# uc2B.net
KiCad netlist of a schematic drawn in Altium Designer
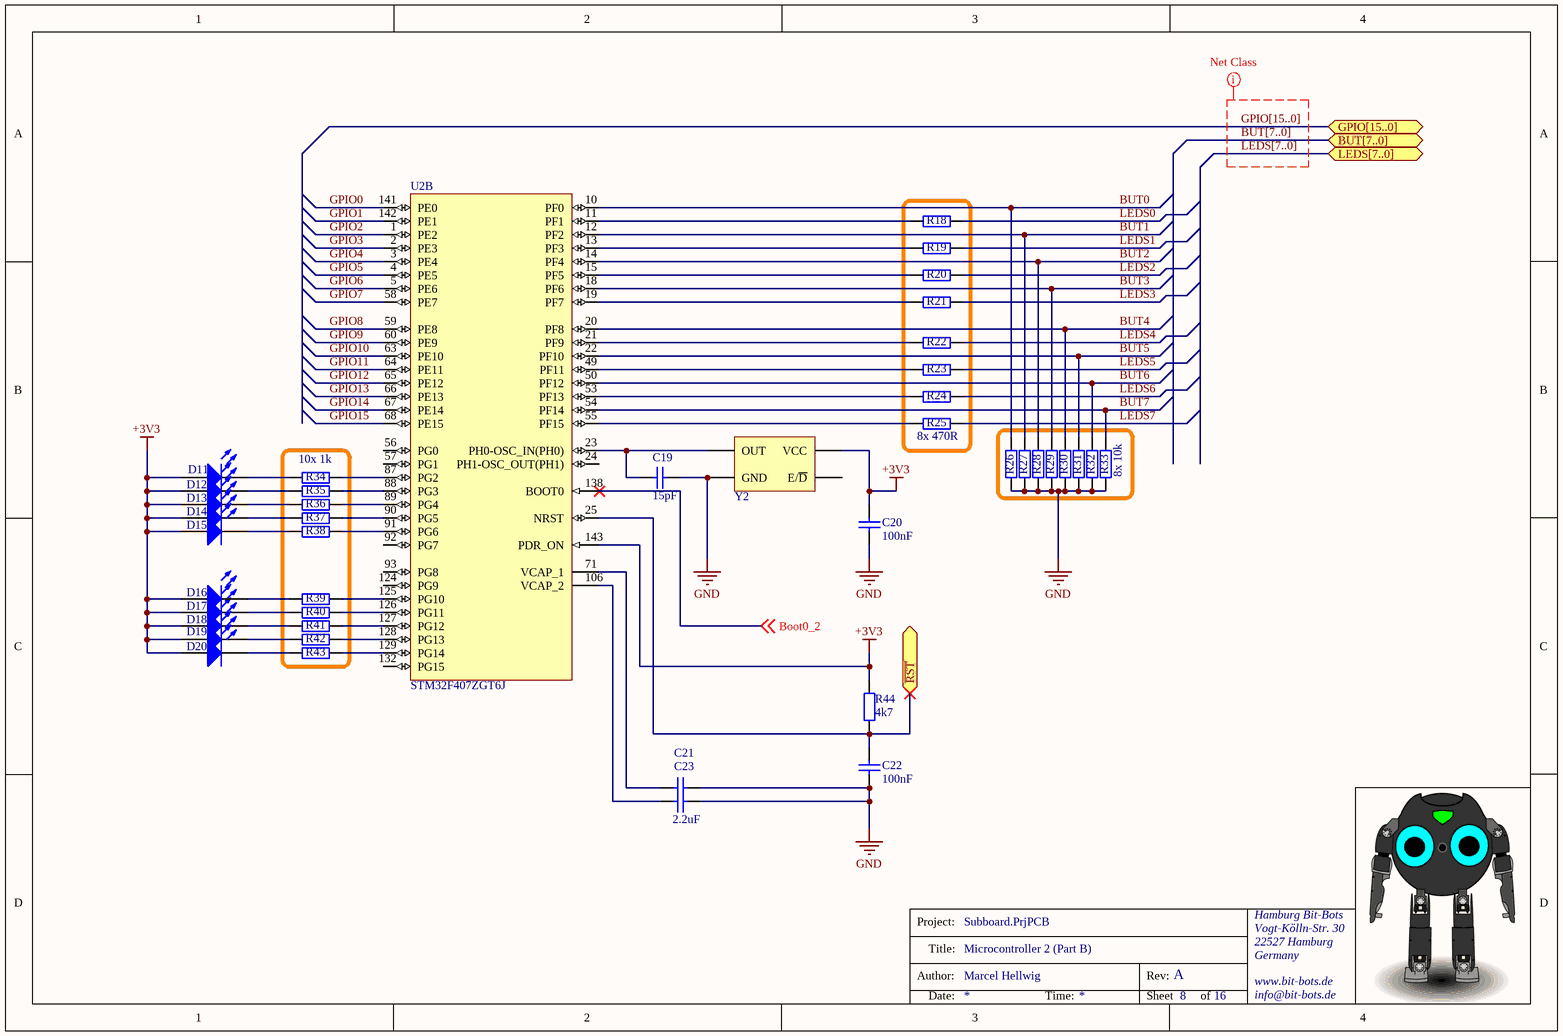
[diagram p0: uc2B.SchDoc]

(export (version "E")
  (design (tool "Eeschema 10.0.6"))
  (components
    (comp (ref "C19")
      (value "15pF")
      (footprint "C2012")
      (description "Capacitor")
      (fields
        (field (name "MANUFACTURER") "MULTICOMP")
        (field (name "MANUFACTURER PART NUMBER") "MC0805N150J500CT")
        (field (name "PUBLISHER") "Altium Limited")
      )
      (libsource (lib "Miscellaneous Devices") (part "Cap"))
    )
    (comp (ref "C20")
      (value "100nF")
      (footprint "C2012")
      (description "Capacitor")
      (fields (field (name "PUBLISHER") "Altium Limited"))
      (libsource (lib "Miscellaneous Devices") (part "Cap"))
    )
    (comp (ref "C21")
      (value "2.2uF")
      (footprint "C2012")
      (description "Capacitor")
      (fields
        (field (name "MANUFACTURER") "MULTICOMP")
        (field (name "MANUFACTURER PART NUMBER") "MC0805B225K250CT")
        (field (name "PUBLISHER") "Altium Limited")
      )
      (libsource (lib "Miscellaneous Devices") (part "Cap"))
    )
    (comp (ref "C22")
      (value "100nF")
      (footprint "C2012")
      (description "Capacitor")
      (fields
        (field (name "MANUFACTURER") "MULTICOMP")
        (field (name "MANUFACTURER PART NUMBER") "MC0805B104K500CT")
        (field (name "PUBLISHER") "Altium Limited")
      )
      (libsource (lib "Miscellaneous Devices") (part "Cap"))
    )
    (comp (ref "C23")
      (value "2.2uF")
      (footprint "C2012")
      (description "Capacitor")
      (fields
        (field (name "MANUFACTURER") "MULTICOMP")
        (field (name "MANUFACTURER PART NUMBER") "MC0805B225K250CT")
        (field (name "PUBLISHER") "Altium Limited")
      )
      (libsource (lib "Miscellaneous Devices") (part "Cap"))
    )
    (comp (ref "D11")
      (value "Green")
      (footprint "MLCC2")
      (description "Typical INFRARED GaAs LED")
      (fields
        (field (name "MANUFACTURER") "VISHAY")
        (field (name "MANUFACTURER PART NUMBER") "VLMC3100-GS08")
        (field (name "PUBLISHER") "Altium Limited")
      )
      (libsource (lib "Miscellaneous Devices") (part "LED0"))
    )
    (comp (ref "D12")
      (value "Green")
      (footprint "MLCC2")
      (description "Typical INFRARED GaAs LED")
      (fields
        (field (name "MANUFACTURER") "VISHAY")
        (field (name "MANUFACTURER PART NUMBER") "VLMC3100-GS08")
        (field (name "PUBLISHER") "Altium Limited")
      )
      (libsource (lib "Miscellaneous Devices") (part "LED0"))
    )
    (comp (ref "D13")
      (value "Green")
      (footprint "MLCC2")
      (description "Typical INFRARED GaAs LED")
      (fields
        (field (name "MANUFACTURER") "VISHAY")
        (field (name "MANUFACTURER PART NUMBER") "VLMC3100-GS08")
        (field (name "PUBLISHER") "Altium Limited")
      )
      (libsource (lib "Miscellaneous Devices") (part "LED0"))
    )
    (comp (ref "D14")
      (value "Green")
      (footprint "MLCC2")
      (description "Typical INFRARED GaAs LED")
      (fields
        (field (name "MANUFACTURER") "VISHAY")
        (field (name "MANUFACTURER PART NUMBER") "VLMC3100-GS08")
        (field (name "PUBLISHER") "Altium Limited")
      )
      (libsource (lib "Miscellaneous Devices") (part "LED0"))
    )
    (comp (ref "D15")
      (value "Green")
      (footprint "MLCC2")
      (description "Typical INFRARED GaAs LED")
      (fields
        (field (name "MANUFACTURER") "VISHAY")
        (field (name "MANUFACTURER PART NUMBER") "VLMC3100-GS08")
        (field (name "PUBLISHER") "Altium Limited")
      )
      (libsource (lib "Miscellaneous Devices") (part "LED0"))
    )
    (comp (ref "D16")
      (value "Green")
      (footprint "MLCC2")
      (description "Typical INFRARED GaAs LED")
      (fields
        (field (name "MANUFACTURER") "VISHAY")
        (field (name "MANUFACTURER PART NUMBER") "VLMC3100-GS08")
        (field (name "PUBLISHER") "Altium Limited")
      )
      (libsource (lib "Miscellaneous Devices") (part "LED0"))
    )
    (comp (ref "D17")
      (value "Green")
      (footprint "MLCC2")
      (description "Typical INFRARED GaAs LED")
      (fields
        (field (name "MANUFACTURER") "VISHAY")
        (field (name "MANUFACTURER PART NUMBER") "VLMC3100-GS08")
        (field (name "PUBLISHER") "Altium Limited")
      )
      (libsource (lib "Miscellaneous Devices") (part "LED0"))
    )
    (comp (ref "D18")
      (value "Green")
      (footprint "MLCC2")
      (description "Typical INFRARED GaAs LED")
      (fields
        (field (name "MANUFACTURER") "VISHAY")
        (field (name "MANUFACTURER PART NUMBER") "VLMC3100-GS08")
        (field (name "PUBLISHER") "Altium Limited")
      )
      (libsource (lib "Miscellaneous Devices") (part "LED0"))
    )
    (comp (ref "D19")
      (value "Green")
      (footprint "MLCC2")
      (description "Typical INFRARED GaAs LED")
      (fields
        (field (name "MANUFACTURER") "VISHAY")
        (field (name "MANUFACTURER PART NUMBER") "VLMC3100-GS08")
        (field (name "PUBLISHER") "Altium Limited")
      )
      (libsource (lib "Miscellaneous Devices") (part "LED0"))
    )
    (comp (ref "D20")
      (value "Green")
      (footprint "MLCC2")
      (description "Typical INFRARED GaAs LED")
      (fields
        (field (name "MANUFACTURER") "VISHAY")
        (field (name "MANUFACTURER PART NUMBER") "VLMC3100-GS08")
        (field (name "PUBLISHER") "Altium Limited")
      )
      (libsource (lib "Miscellaneous Devices") (part "LED0"))
    )
    (comp (ref "R18")
      (value "470R")
      (footprint "R2012")
      (description "Resistor")
      (fields
        (field (name "MANUFACTURER") "MULTICOMP")
        (field (name "MANUFACTURER PART NUMBER") "MCSR08X4700FTL")
        (field (name "PUBLISHER") "Altium Limited")
      )
      (libsource (lib "") (part "Res2_2"))
    )
    (comp (ref "R19")
      (value "470R")
      (footprint "R2012")
      (description "Resistor")
      (fields
        (field (name "MANUFACTURER") "MULTICOMP")
        (field (name "MANUFACTURER PART NUMBER") "MCSR08X4700FTL")
        (field (name "PUBLISHER") "Altium Limited")
      )
      (libsource (lib "") (part "Res2_2"))
    )
    (comp (ref "R20")
      (value "470R")
      (footprint "R2012")
      (description "Resistor")
      (fields
        (field (name "MANUFACTURER") "MULTICOMP")
        (field (name "MANUFACTURER PART NUMBER") "MCSR08X4700FTL")
        (field (name "PUBLISHER") "Altium Limited")
      )
      (libsource (lib "") (part "Res2_2"))
    )
    (comp (ref "R21")
      (value "470R")
      (footprint "R2012")
      (description "Resistor")
      (fields
        (field (name "MANUFACTURER") "MULTICOMP")
        (field (name "MANUFACTURER PART NUMBER") "MCSR08X4700FTL")
        (field (name "PUBLISHER") "Altium Limited")
      )
      (libsource (lib "") (part "Res2_2"))
    )
    (comp (ref "R22")
      (value "470R")
      (footprint "R2012")
      (description "Resistor")
      (fields
        (field (name "MANUFACTURER") "MULTICOMP")
        (field (name "MANUFACTURER PART NUMBER") "MCSR08X4700FTL")
        (field (name "PUBLISHER") "Altium Limited")
      )
      (libsource (lib "") (part "Res2_2"))
    )
    (comp (ref "R23")
      (value "470R")
      (footprint "R2012")
      (description "Resistor")
      (fields
        (field (name "MANUFACTURER") "MULTICOMP")
        (field (name "MANUFACTURER PART NUMBER") "MCSR08X4700FTL")
        (field (name "PUBLISHER") "Altium Limited")
      )
      (libsource (lib "") (part "Res2_2"))
    )
    (comp (ref "R24")
      (value "470R")
      (footprint "R2012")
      (description "Resistor")
      (fields
        (field (name "MANUFACTURER") "MULTICOMP")
        (field (name "MANUFACTURER PART NUMBER") "MCSR08X4700FTL")
        (field (name "PUBLISHER") "Altium Limited")
      )
      (libsource (lib "") (part "Res2_2"))
    )
    (comp (ref "R25")
      (value "470R")
      (footprint "R2012")
      (description "Resistor")
      (fields
        (field (name "MANUFACTURER") "MULTICOMP")
        (field (name "MANUFACTURER PART NUMBER") "MCSR08X4700FTL")
        (field (name "PUBLISHER") "Altium Limited")
      )
      (libsource (lib "") (part "Res2_2"))
    )
    (comp (ref "R26")
      (value "10k")
      (footprint "R2012")
      (description "Resistor")
      (fields
        (field (name "MANUFACTURER") "MULTICOMP")
        (field (name "MANUFACTURER PART NUMBER") "MC01W0805110K")
        (field (name "PUBLISHER") "Altium Limited")
      )
      (libsource (lib "Miscellaneous Devices") (part "Res2"))
    )
    (comp (ref "R27")
      (value "10k")
      (footprint "R2012")
      (description "Resistor")
      (fields
        (field (name "MANUFACTURER") "MULTICOMP")
        (field (name "MANUFACTURER PART NUMBER") "MC01W0805110K")
        (field (name "PUBLISHER") "Altium Limited")
      )
      (libsource (lib "Miscellaneous Devices") (part "Res2"))
    )
    (comp (ref "R28")
      (value "10k")
      (footprint "R2012")
      (description "Resistor")
      (fields
        (field (name "MANUFACTURER") "MULTICOMP")
        (field (name "MANUFACTURER PART NUMBER") "MC01W0805110K")
        (field (name "PUBLISHER") "Altium Limited")
      )
      (libsource (lib "Miscellaneous Devices") (part "Res2"))
    )
    (comp (ref "R29")
      (value "10k")
      (footprint "R2012")
      (description "Resistor")
      (fields
        (field (name "MANUFACTURER") "MULTICOMP")
        (field (name "MANUFACTURER PART NUMBER") "MC01W0805110K")
        (field (name "PUBLISHER") "Altium Limited")
      )
      (libsource (lib "Miscellaneous Devices") (part "Res2"))
    )
    (comp (ref "R30")
      (value "10k")
      (footprint "R2012")
      (description "Resistor")
      (fields
        (field (name "MANUFACTURER") "MULTICOMP")
        (field (name "MANUFACTURER PART NUMBER") "MC01W0805110K")
        (field (name "PUBLISHER") "Altium Limited")
      )
      (libsource (lib "Miscellaneous Devices") (part "Res2"))
    )
    (comp (ref "R31")
      (value "10k")
      (footprint "R2012")
      (description "Resistor")
      (fields
        (field (name "MANUFACTURER") "MULTICOMP")
        (field (name "MANUFACTURER PART NUMBER") "MC01W0805110K")
        (field (name "PUBLISHER") "Altium Limited")
      )
      (libsource (lib "Miscellaneous Devices") (part "Res2"))
    )
    (comp (ref "R32")
      (value "10k")
      (footprint "R2012")
      (description "Resistor")
      (fields
        (field (name "MANUFACTURER") "MULTICOMP")
        (field (name "MANUFACTURER PART NUMBER") "MC01W0805110K")
        (field (name "PUBLISHER") "Altium Limited")
      )
      (libsource (lib "Miscellaneous Devices") (part "Res2"))
    )
    (comp (ref "R33")
      (value "10k")
      (footprint "R2012")
      (description "Resistor")
      (fields
        (field (name "MANUFACTURER") "MULTICOMP")
        (field (name "MANUFACTURER PART NUMBER") "MC01W0805110K")
        (field (name "PUBLISHER") "Altium Limited")
      )
      (libsource (lib "Miscellaneous Devices") (part "Res2"))
    )
    (comp (ref "R34")
      (value "1k")
      (footprint "R2012")
      (description "Resistor")
      (fields
        (field (name "MANUFACTURER") "MULTICOMP")
        (field (name "MANUFACTURER PART NUMBER") "MC01W0805110K")
        (field (name "PUBLISHER") "Altium Limited")
      )
      (libsource (lib "") (part "Res2_1"))
    )
    (comp (ref "R35")
      (value "1k")
      (footprint "R2012")
      (description "Resistor")
      (fields
        (field (name "MANUFACTURER") "MULTICOMP")
        (field (name "MANUFACTURER PART NUMBER") "MC01W0805110K")
        (field (name "PUBLISHER") "Altium Limited")
      )
      (libsource (lib "") (part "Res2_1"))
    )
    (comp (ref "R36")
      (value "1k")
      (footprint "R2012")
      (description "Resistor")
      (fields
        (field (name "MANUFACTURER") "MULTICOMP")
        (field (name "MANUFACTURER PART NUMBER") "MC01W0805110K")
        (field (name "PUBLISHER") "Altium Limited")
      )
      (libsource (lib "") (part "Res2_1"))
    )
    (comp (ref "R37")
      (value "1k")
      (footprint "R2012")
      (description "Resistor")
      (fields
        (field (name "MANUFACTURER") "MULTICOMP")
        (field (name "MANUFACTURER PART NUMBER") "MC01W0805110K")
        (field (name "PUBLISHER") "Altium Limited")
      )
      (libsource (lib "") (part "Res2_1"))
    )
    (comp (ref "R38")
      (value "1k")
      (footprint "R2012")
      (description "Resistor")
      (fields
        (field (name "MANUFACTURER") "MULTICOMP")
        (field (name "MANUFACTURER PART NUMBER") "MC01W0805110K")
        (field (name "PUBLISHER") "Altium Limited")
      )
      (libsource (lib "") (part "Res2_1"))
    )
    (comp (ref "R39")
      (value "1k")
      (footprint "R2012")
      (description "Resistor")
      (fields
        (field (name "MANUFACTURER") "MULTICOMP")
        (field (name "MANUFACTURER PART NUMBER") "MC01W0805110K")
        (field (name "PUBLISHER") "Altium Limited")
      )
      (libsource (lib "") (part "Res2_1"))
    )
    (comp (ref "R40")
      (value "1k")
      (footprint "R2012")
      (description "Resistor")
      (fields
        (field (name "MANUFACTURER") "MULTICOMP")
        (field (name "MANUFACTURER PART NUMBER") "MC01W0805110K")
        (field (name "PUBLISHER") "Altium Limited")
      )
      (libsource (lib "") (part "Res2_1"))
    )
    (comp (ref "R41")
      (value "1k")
      (footprint "R2012")
      (description "Resistor")
      (fields
        (field (name "MANUFACTURER") "MULTICOMP")
        (field (name "MANUFACTURER PART NUMBER") "MC01W0805110K")
        (field (name "PUBLISHER") "Altium Limited")
      )
      (libsource (lib "") (part "Res2_1"))
    )
    (comp (ref "R42")
      (value "1k")
      (footprint "R2012")
      (description "Resistor")
      (fields
        (field (name "MANUFACTURER") "MULTICOMP")
        (field (name "MANUFACTURER PART NUMBER") "MC01W0805110K")
        (field (name "PUBLISHER") "Altium Limited")
      )
      (libsource (lib "") (part "Res2_1"))
    )
    (comp (ref "R43")
      (value "1k")
      (footprint "R2012")
      (description "Resistor")
      (fields
        (field (name "MANUFACTURER") "MULTICOMP")
        (field (name "MANUFACTURER PART NUMBER") "MC01W0805110K")
        (field (name "PUBLISHER") "Altium Limited")
      )
      (libsource (lib "") (part "Res2_1"))
    )
    (comp (ref "R44")
      (value "4k7")
      (footprint "R2012")
      (description "Resistor")
      (fields
        (field (name "MANUFACTURER") "MULTICOMP")
        (field (name "MANUFACTURER PART NUMBER") "MC01W080514K7")
        (field (name "PUBLISHER") "Altium Limited")
      )
      (libsource (lib "Miscellaneous Devices") (part "Res2"))
    )
    (comp (ref "U2")
      (value "STM32F407ZGT6J")
      (footprint "STM-LQFP144_M")
      (fields (field (name "MANUFACTURER") "STMicroelectronics"))
      (libsource (lib "Altium Content Vault") (part "CMP-0243-00063-2"))
    )
    (comp (ref "Y2")
      (value "FXO-HC736R-16")
      (footprint "FXO-HC73")
      (description "Oscillator with Enable Input")
      (libsource (lib "bitbots") (part "Oszillator"))
    )
  )
  (nets
    (net (code "1") (name "+3V3") (class "Default")
      (node (ref "C20") (pin "1") (pinfunction "1_1") (pintype "passive"))
      (node (ref "D11") (pin "1") (pinfunction "A_1") (pintype "passive"))
      (node (ref "D12") (pin "1") (pinfunction "A_1") (pintype "passive"))
      (node (ref "D13") (pin "1") (pinfunction "A_1") (pintype "passive"))
      (node (ref "D14") (pin "1") (pinfunction "A_1") (pintype "passive"))
      (node (ref "D15") (pin "1") (pinfunction "A_1") (pintype "passive"))
      (node (ref "D16") (pin "1") (pinfunction "A_1") (pintype "passive"))
      (node (ref "D17") (pin "1") (pinfunction "A_1") (pintype "passive"))
      (node (ref "D18") (pin "1") (pinfunction "A_1") (pintype "passive"))
      (node (ref "D19") (pin "1") (pinfunction "A_1") (pintype "passive"))
      (node (ref "D20") (pin "1") (pinfunction "A_1") (pintype "passive"))
      (node (ref "R44") (pin "1") (pinfunction "1_1") (pintype "passive"))
      (node (ref "U2") (pin "143") (pinfunction "PDR_ON_143") (pintype "input"))
      (node (ref "Y2") (pin "4") (pinfunction "VCC_4") (pintype "passive"))
    )
    (net (code "2") (name "/BUT0") (class "Default")
      (node (ref "R26") (pin "1") (pinfunction "1_1") (pintype "passive"))
      (node (ref "U2") (pin "10") (pinfunction "PF0_10") (pintype "bidirectional"))
    )
    (net (code "3") (name "/BUT1") (class "Default")
      (node (ref "R27") (pin "1") (pinfunction "1_1") (pintype "passive"))
      (node (ref "U2") (pin "12") (pinfunction "PF2_12") (pintype "bidirectional"))
    )
    (net (code "4") (name "/BUT2") (class "Default")
      (node (ref "R28") (pin "1") (pinfunction "1_1") (pintype "passive"))
      (node (ref "U2") (pin "14") (pinfunction "PF4_14") (pintype "bidirectional"))
    )
    (net (code "5") (name "/BUT3") (class "Default")
      (node (ref "R29") (pin "1") (pinfunction "1_1") (pintype "passive"))
      (node (ref "U2") (pin "18") (pinfunction "PF6_18") (pintype "bidirectional"))
    )
    (net (code "6") (name "/BUT4") (class "Default")
      (node (ref "R30") (pin "1") (pinfunction "1_1") (pintype "passive"))
      (node (ref "U2") (pin "20") (pinfunction "PF8_20") (pintype "bidirectional"))
    )
    (net (code "7") (name "/BUT5") (class "Default")
      (node (ref "R31") (pin "1") (pinfunction "1_1") (pintype "passive"))
      (node (ref "U2") (pin "22") (pinfunction "PF10_22") (pintype "bidirectional"))
    )
    (net (code "8") (name "/BUT6") (class "Default")
      (node (ref "R32") (pin "1") (pinfunction "1_1") (pintype "passive"))
      (node (ref "U2") (pin "50") (pinfunction "PF12_50") (pintype "bidirectional"))
    )
    (net (code "9") (name "/BUT7") (class "Default")
      (node (ref "R33") (pin "1") (pinfunction "1_1") (pintype "passive"))
      (node (ref "U2") (pin "54") (pinfunction "PF14_54") (pintype "bidirectional"))
    )
    (net (code "11") (name "/GPIO0") (class "Default")
      (node (ref "U2") (pin "141") (pinfunction "PE0_141") (pintype "bidirectional"))
    )
    (net (code "12") (name "/GPIO1") (class "Default")
      (node (ref "U2") (pin "142") (pinfunction "PE1_142") (pintype "bidirectional"))
    )
    (net (code "13") (name "/GPIO2") (class "Default")
      (node (ref "U2") (pin "1") (pinfunction "PE2_1") (pintype "bidirectional"))
    )
    (net (code "14") (name "/GPIO3") (class "Default")
      (node (ref "U2") (pin "2") (pinfunction "PE3_2") (pintype "bidirectional"))
    )
    (net (code "15") (name "/GPIO4") (class "Default")
      (node (ref "U2") (pin "3") (pinfunction "PE4_3") (pintype "bidirectional"))
    )
    (net (code "16") (name "/GPIO5") (class "Default")
      (node (ref "U2") (pin "4") (pinfunction "PE5_4") (pintype "bidirectional"))
    )
    (net (code "17") (name "/GPIO6") (class "Default")
      (node (ref "U2") (pin "5") (pinfunction "PE6_5") (pintype "bidirectional"))
    )
    (net (code "18") (name "/GPIO7") (class "Default")
      (node (ref "U2") (pin "58") (pinfunction "PE7_58") (pintype "bidirectional"))
    )
    (net (code "19") (name "/GPIO8") (class "Default")
      (node (ref "U2") (pin "59") (pinfunction "PE8_59") (pintype "bidirectional"))
    )
    (net (code "20") (name "/GPIO9") (class "Default")
      (node (ref "U2") (pin "60") (pinfunction "PE9_60") (pintype "bidirectional"))
    )
    (net (code "21") (name "/GPIO10") (class "Default")
      (node (ref "U2") (pin "63") (pinfunction "PE10_63") (pintype "bidirectional"))
    )
    (net (code "22") (name "/GPIO11") (class "Default")
      (node (ref "U2") (pin "64") (pinfunction "PE11_64") (pintype "bidirectional"))
    )
    (net (code "23") (name "/GPIO12") (class "Default")
      (node (ref "U2") (pin "65") (pinfunction "PE12_65") (pintype "bidirectional"))
    )
    (net (code "24") (name "/GPIO13") (class "Default")
      (node (ref "U2") (pin "66") (pinfunction "PE13_66") (pintype "bidirectional"))
    )
    (net (code "25") (name "/GPIO14") (class "Default")
      (node (ref "U2") (pin "67") (pinfunction "PE14_67") (pintype "bidirectional"))
    )
    (net (code "26") (name "/GPIO15") (class "Default")
      (node (ref "U2") (pin "68") (pinfunction "PE15_68") (pintype "bidirectional"))
    )
    (net (code "28") (name "/LEDS0") (class "Default")
      (node (ref "R18") (pin "2") (pinfunction "2_2") (pintype "passive"))
    )
    (net (code "29") (name "/LEDS1") (class "Default")
      (node (ref "R19") (pin "2") (pinfunction "2_2") (pintype "passive"))
    )
    (net (code "30") (name "/LEDS2") (class "Default")
      (node (ref "R20") (pin "2") (pinfunction "2_2") (pintype "passive"))
    )
    (net (code "31") (name "/LEDS3") (class "Default")
      (node (ref "R21") (pin "2") (pinfunction "2_2") (pintype "passive"))
    )
    (net (code "32") (name "/LEDS4") (class "Default")
      (node (ref "R22") (pin "2") (pinfunction "2_2") (pintype "passive"))
    )
    (net (code "33") (name "/LEDS5") (class "Default")
      (node (ref "R23") (pin "2") (pinfunction "2_2") (pintype "passive"))
    )
    (net (code "34") (name "/LEDS6") (class "Default")
      (node (ref "R24") (pin "2") (pinfunction "2_2") (pintype "passive"))
    )
    (net (code "35") (name "/LEDS7") (class "Default")
      (node (ref "R25") (pin "2") (pinfunction "2_2") (pintype "passive"))
    )
    (net (code "37") (name "/RST") (class "Default")
      (node (ref "C22") (pin "2") (pinfunction "2_2") (pintype "passive"))
      (node (ref "R44") (pin "2") (pinfunction "2_2") (pintype "passive"))
      (node (ref "U2") (pin "25") (pinfunction "NRST_25") (pintype "bidirectional"))
    )
    (net (code "38") (name "Boot0_2") (class "Default")
      (node (ref "U2") (pin "138") (pinfunction "BOOT0_138") (pintype "input"))
    )
    (net (code "39") (name "GND") (class "Default")
      (node (ref "C19") (pin "1") (pinfunction "1_1") (pintype "passive"))
      (node (ref "C20") (pin "2") (pinfunction "2_2") (pintype "passive"))
      (node (ref "C21") (pin "2") (pinfunction "2_2") (pintype "passive"))
      (node (ref "C22") (pin "1") (pinfunction "1_1") (pintype "passive"))
      (node (ref "C23") (pin "2") (pinfunction "2_2") (pintype "passive"))
      (node (ref "R26") (pin "2") (pinfunction "2_2") (pintype "passive"))
      (node (ref "R27") (pin "2") (pinfunction "2_2") (pintype "passive"))
      (node (ref "R28") (pin "2") (pinfunction "2_2") (pintype "passive"))
      (node (ref "R29") (pin "2") (pinfunction "2_2") (pintype "passive"))
      (node (ref "R30") (pin "2") (pinfunction "2_2") (pintype "passive"))
      (node (ref "R31") (pin "2") (pinfunction "2_2") (pintype "passive"))
      (node (ref "R32") (pin "2") (pinfunction "2_2") (pintype "passive"))
      (node (ref "R33") (pin "2") (pinfunction "2_2") (pintype "passive"))
      (node (ref "Y2") (pin "2") (pinfunction "GND_2") (pintype "passive"))
    )
    (net (code "40") (name "Net-(D11-K)") (class "Default")
      (node (ref "D11") (pin "2") (pinfunction "K_2") (pintype "passive"))
      (node (ref "R34") (pin "2") (pinfunction "2_2") (pintype "passive"))
    )
    (net (code "41") (name "Net-(D12-K)") (class "Default")
      (node (ref "D12") (pin "2") (pinfunction "K_2") (pintype "passive"))
      (node (ref "R35") (pin "2") (pinfunction "2_2") (pintype "passive"))
    )
    (net (code "42") (name "Net-(D13-K)") (class "Default")
      (node (ref "D13") (pin "2") (pinfunction "K_2") (pintype "passive"))
      (node (ref "R36") (pin "2") (pinfunction "2_2") (pintype "passive"))
    )
    (net (code "43") (name "Net-(D14-K)") (class "Default")
      (node (ref "D14") (pin "2") (pinfunction "K_2") (pintype "passive"))
      (node (ref "R37") (pin "2") (pinfunction "2_2") (pintype "passive"))
    )
    (net (code "44") (name "Net-(D15-K)") (class "Default")
      (node (ref "D15") (pin "2") (pinfunction "K_2") (pintype "passive"))
      (node (ref "R38") (pin "2") (pinfunction "2_2") (pintype "passive"))
    )
    (net (code "45") (name "Net-(D16-K)") (class "Default")
      (node (ref "D16") (pin "2") (pinfunction "K_2") (pintype "passive"))
      (node (ref "R39") (pin "2") (pinfunction "2_2") (pintype "passive"))
    )
    (net (code "46") (name "Net-(D17-K)") (class "Default")
      (node (ref "D17") (pin "2") (pinfunction "K_2") (pintype "passive"))
      (node (ref "R40") (pin "2") (pinfunction "2_2") (pintype "passive"))
    )
    (net (code "47") (name "Net-(D18-K)") (class "Default")
      (node (ref "D18") (pin "2") (pinfunction "K_2") (pintype "passive"))
      (node (ref "R41") (pin "2") (pinfunction "2_2") (pintype "passive"))
    )
    (net (code "48") (name "Net-(D19-K)") (class "Default")
      (node (ref "D19") (pin "2") (pinfunction "K_2") (pintype "passive"))
      (node (ref "R42") (pin "2") (pinfunction "2_2") (pintype "passive"))
    )
    (net (code "49") (name "Net-(D20-K)") (class "Default")
      (node (ref "D20") (pin "2") (pinfunction "K_2") (pintype "passive"))
      (node (ref "R43") (pin "2") (pinfunction "2_2") (pintype "passive"))
    )
    (net (code "50") (name "Net-(U2B-PF1)") (class "Default")
      (node (ref "R18") (pin "1") (pinfunction "1_1") (pintype "passive"))
      (node (ref "U2") (pin "11") (pinfunction "PF1_11") (pintype "bidirectional"))
    )
    (net (code "51") (name "Net-(U2B-PF3)") (class "Default")
      (node (ref "R19") (pin "1") (pinfunction "1_1") (pintype "passive"))
      (node (ref "U2") (pin "13") (pinfunction "PF3_13") (pintype "bidirectional"))
    )
    (net (code "52") (name "Net-(U2B-PF5)") (class "Default")
      (node (ref "R20") (pin "1") (pinfunction "1_1") (pintype "passive"))
      (node (ref "U2") (pin "15") (pinfunction "PF5_15") (pintype "bidirectional"))
    )
    (net (code "53") (name "Net-(U2B-PF7)") (class "Default")
      (node (ref "R21") (pin "1") (pinfunction "1_1") (pintype "passive"))
      (node (ref "U2") (pin "19") (pinfunction "PF7_19") (pintype "bidirectional"))
    )
    (net (code "54") (name "Net-(U2B-PF9)") (class "Default")
      (node (ref "R22") (pin "1") (pinfunction "1_1") (pintype "passive"))
      (node (ref "U2") (pin "21") (pinfunction "PF9_21") (pintype "bidirectional"))
    )
    (net (code "55") (name "Net-(U2B-PF11)") (class "Default")
      (node (ref "R23") (pin "1") (pinfunction "1_1") (pintype "passive"))
      (node (ref "U2") (pin "49") (pinfunction "PF11_49") (pintype "bidirectional"))
    )
    (net (code "56") (name "Net-(U2B-PF13)") (class "Default")
      (node (ref "R24") (pin "1") (pinfunction "1_1") (pintype "passive"))
      (node (ref "U2") (pin "53") (pinfunction "PF13_53") (pintype "bidirectional"))
    )
    (net (code "57") (name "Net-(U2B-PF15)") (class "Default")
      (node (ref "R25") (pin "1") (pinfunction "1_1") (pintype "passive"))
      (node (ref "U2") (pin "55") (pinfunction "PF15_55") (pintype "bidirectional"))
    )
    (net (code "58") (name "Net-(U2B-PG2)") (class "Default")
      (node (ref "R34") (pin "1") (pinfunction "1_1") (pintype "passive"))
      (node (ref "U2") (pin "87") (pinfunction "PG2_87") (pintype "bidirectional"))
    )
    (net (code "59") (name "Net-(U2B-PG3)") (class "Default")
      (node (ref "R35") (pin "1") (pinfunction "1_1") (pintype "passive"))
      (node (ref "U2") (pin "88") (pinfunction "PG3_88") (pintype "bidirectional"))
    )
    (net (code "60") (name "Net-(U2B-PG4)") (class "Default")
      (node (ref "R36") (pin "1") (pinfunction "1_1") (pintype "passive"))
      (node (ref "U2") (pin "89") (pinfunction "PG4_89") (pintype "bidirectional"))
    )
    (net (code "61") (name "Net-(U2B-PG5)") (class "Default")
      (node (ref "R37") (pin "1") (pinfunction "1_1") (pintype "passive"))
      (node (ref "U2") (pin "90") (pinfunction "PG5_90") (pintype "bidirectional"))
    )
    (net (code "62") (name "Net-(U2B-PG6)") (class "Default")
      (node (ref "R38") (pin "1") (pinfunction "1_1") (pintype "passive"))
      (node (ref "U2") (pin "91") (pinfunction "PG6_91") (pintype "bidirectional"))
    )
    (net (code "63") (name "Net-(U2B-PG10)") (class "Default")
      (node (ref "R39") (pin "1") (pinfunction "1_1") (pintype "passive"))
      (node (ref "U2") (pin "125") (pinfunction "PG10_125") (pintype "bidirectional"))
    )
    (net (code "64") (name "Net-(U2B-PG11)") (class "Default")
      (node (ref "R40") (pin "1") (pinfunction "1_1") (pintype "passive"))
      (node (ref "U2") (pin "126") (pinfunction "PG11_126") (pintype "bidirectional"))
    )
    (net (code "65") (name "Net-(U2B-PG12)") (class "Default")
      (node (ref "R41") (pin "1") (pinfunction "1_1") (pintype "passive"))
      (node (ref "U2") (pin "127") (pinfunction "PG12_127") (pintype "bidirectional"))
    )
    (net (code "66") (name "Net-(U2B-PG13)") (class "Default")
      (node (ref "R42") (pin "1") (pinfunction "1_1") (pintype "passive"))
      (node (ref "U2") (pin "128") (pinfunction "PG13_128") (pintype "bidirectional"))
    )
    (net (code "67") (name "Net-(U2B-PG14)") (class "Default")
      (node (ref "R43") (pin "1") (pinfunction "1_1") (pintype "passive"))
      (node (ref "U2") (pin "129") (pinfunction "PG14_129") (pintype "bidirectional"))
    )
    (net (code "68") (name "Net-(U2B-PH0-OSC_IN(PH0))") (class "Default")
      (node (ref "C19") (pin "2") (pinfunction "2_2") (pintype "passive"))
      (node (ref "U2") (pin "23") (pinfunction "PH0-OSC_IN(PH0)_23") (pintype "bidirectional"))
      (node (ref "Y2") (pin "3") (pinfunction "OUT_3") (pintype "passive"))
    )
    (net (code "69") (name "Net-(U2B-VCAP_1)") (class "Default")
      (node (ref "C21") (pin "1") (pinfunction "1_1") (pintype "passive"))
      (node (ref "U2") (pin "71") (pinfunction "VCAP_1_71") (pintype "power_in"))
    )
    (net (code "70") (name "Net-(U2B-VCAP_2)") (class "Default")
      (node (ref "C23") (pin "1") (pinfunction "1_1") (pintype "passive"))
      (node (ref "U2") (pin "106") (pinfunction "VCAP_2_106") (pintype "power_in"))
    )
    (net (code "71") (name "unconnected-(U2B-PG0-Pad56)") (class "Default")
      (node (ref "U2") (pin "56") (pinfunction "PG0_56") (pintype "bidirectional"))
    )
    (net (code "72") (name "unconnected-(U2B-PG1-Pad57)") (class "Default")
      (node (ref "U2") (pin "57") (pinfunction "PG1_57") (pintype "bidirectional"))
    )
    (net (code "73") (name "unconnected-(U2B-PG7-Pad92)") (class "Default")
      (node (ref "U2") (pin "92") (pinfunction "PG7_92") (pintype "bidirectional"))
    )
    (net (code "74") (name "unconnected-(U2B-PG8-Pad93)") (class "Default")
      (node (ref "U2") (pin "93") (pinfunction "PG8_93") (pintype "bidirectional"))
    )
    (net (code "75") (name "unconnected-(U2B-PG9-Pad124)") (class "Default")
      (node (ref "U2") (pin "124") (pinfunction "PG9_124") (pintype "bidirectional"))
    )
    (net (code "76") (name "unconnected-(U2B-PG15-Pad132)") (class "Default")
      (node (ref "U2") (pin "132") (pinfunction "PG15_132") (pintype "bidirectional"))
    )
    (net (code "77") (name "unconnected-(U2B-PH1-OSC_OUT(PH1)-Pad24)") (class "Default")
      (node (ref "U2") (pin "24") (pinfunction "PH1-OSC_OUT(PH1)_24") (pintype "bidirectional"))
    )
    (net (code "78") (name "unconnected-(Y2-E{slash}~{D}-Pad1)") (class "Default")
      (node (ref "Y2") (pin "1") (pinfunction "E/~{D}_1") (pintype "passive"))
    )
  )
)
